# MICROPHONE.net
KiCad netlist of a schematic drawn in Altium Designer
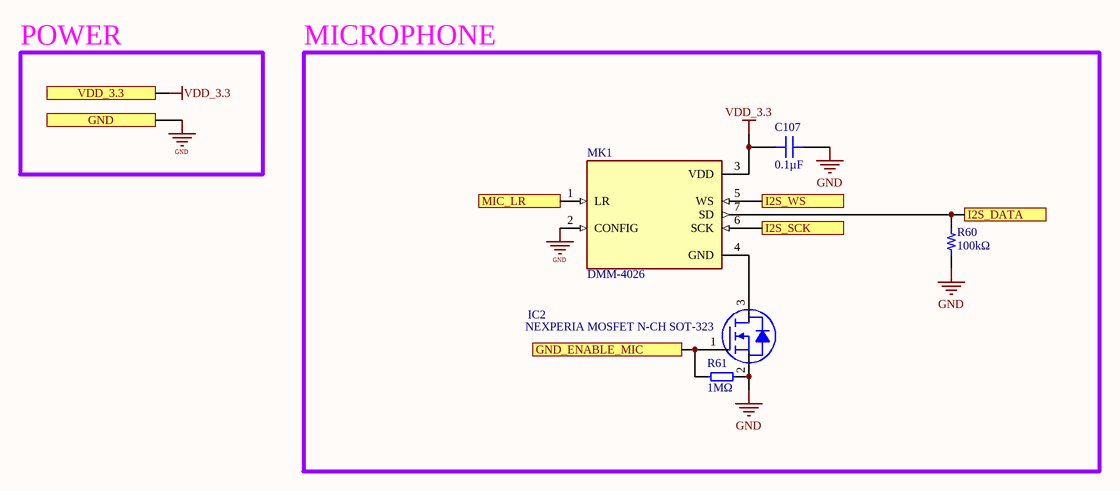
[diagram p0: MICROPHONE.SchDoc]

(export (version "E")
  (design (tool "Eeschema 10.0.6"))
  (components
    (comp (ref "C107")
      (value "0.1µF")
      (footprint "CAP 0603_1608 RF")
      (description "CAP CER 0.1UF 16V X7R 0603")
      (fields (field (name "MANUFACTURER") "KEMET") (field (name "VOLTAGE") "16V"))
      (libsource (lib "MVVVMAltiumDatabase") (part "Capacitor"))
    )
    (comp (ref "IC2")
      (value "NEXPERIA MOSFET N-CH SOT-323")
      (footprint "NEXPERIA SOT-323")
      (description "MOSFET N-CH 60V 320MA SOT323")
      (fields (field (name "MANUFACTURER") "Nexperia USA Inc."))
      (libsource (lib "MVVVMAltiumDatabase") (part "NEXPERIA MOSFET N-CH SOT-323"))
    )
    (comp (ref "MK1")
      (value "DMM-4026")
      (footprint "DMM-4026")
      (description "DIFFERENTIAL ANALOG OUTPUT MEMS")
      (fields
        (field (name "MP") "DMM-4026-B-I2S-R")
        (field (name "DIGI-KEY_PART_NUMBER") "668-DMM-4026-B-I2S-RCT-ND")
      )
      (libsource (lib "MVVVMAltiumDatabase") (part "DMM-4026"))
    )
    (comp (ref "R60")
      (value "100kΩ")
      (footprint "RES 0603_1608 RF")
      (description "RES 100k OHM 1% 1/10W 0603")
      (fields (field (name "MANUFACTURER") "Vishay Dale") (field (name "TOLERANCE") "±1%"))
      (libsource (lib "MVVVMAltiumDatabase") (part "Resistor"))
    )
    (comp (ref "R61")
      (value "1MΩ")
      (footprint "0603_1608 RF")
      (description "0603 RF Passive")
      (libsource (lib "MVVVMAltiumDatabase") (part "RF Passive"))
    )
  )
  (nets
    (net (code "1") (name "/GND_ENABLE_MIC") (class "Default")
      (node (ref "IC2") (pin "1") (pinfunction "G_1") (pintype "passive"))
      (node (ref "R61") (pin "2") (pinfunction "2_2") (pintype "passive"))
    )
    (net (code "2") (name "/I2S_DATA") (class "Default")
      (node (ref "MK1") (pin "7") (pinfunction "SD_7") (pintype "output"))
      (node (ref "R60") (pin "2") (pinfunction "2_2") (pintype "passive"))
    )
    (net (code "3") (name "/I2S_SCK") (class "Default")
      (node (ref "MK1") (pin "6") (pinfunction "SCK_6") (pintype "input"))
    )
    (net (code "4") (name "/I2S_WS") (class "Default")
      (node (ref "MK1") (pin "5") (pinfunction "WS_5") (pintype "input"))
    )
    (net (code "5") (name "/MIC_LR") (class "Default")
      (node (ref "MK1") (pin "1") (pinfunction "LR_1") (pintype "input"))
    )
    (net (code "6") (name "GND") (class "Default")
      (node (ref "C107") (pin "2") (pinfunction "2_2") (pintype "passive"))
      (node (ref "IC2") (pin "2") (pinfunction "S_2") (pintype "passive"))
      (node (ref "MK1") (pin "2") (pinfunction "CONFIG_2") (pintype "input"))
      (node (ref "R60") (pin "1") (pinfunction "1_1") (pintype "passive"))
      (node (ref "R61") (pin "1") (pinfunction "1_1") (pintype "passive"))
    )
    (net (code "7") (name "Net-(IC2-D)") (class "Default")
      (node (ref "IC2") (pin "3") (pinfunction "D_3") (pintype "passive"))
      (node (ref "MK1") (pin "4") (pinfunction "GND_4") (pintype "power_in"))
    )
    (net (code "8") (name "VDD_3.3") (class "Default")
      (node (ref "C107") (pin "1") (pinfunction "1_1") (pintype "passive"))
      (node (ref "MK1") (pin "3") (pinfunction "VDD_3") (pintype "power_in"))
    )
  )
)
